# SCH_The-weather-gian_2026-05-14.net
KiCad netlist of a schematic drawn in EasyEDA
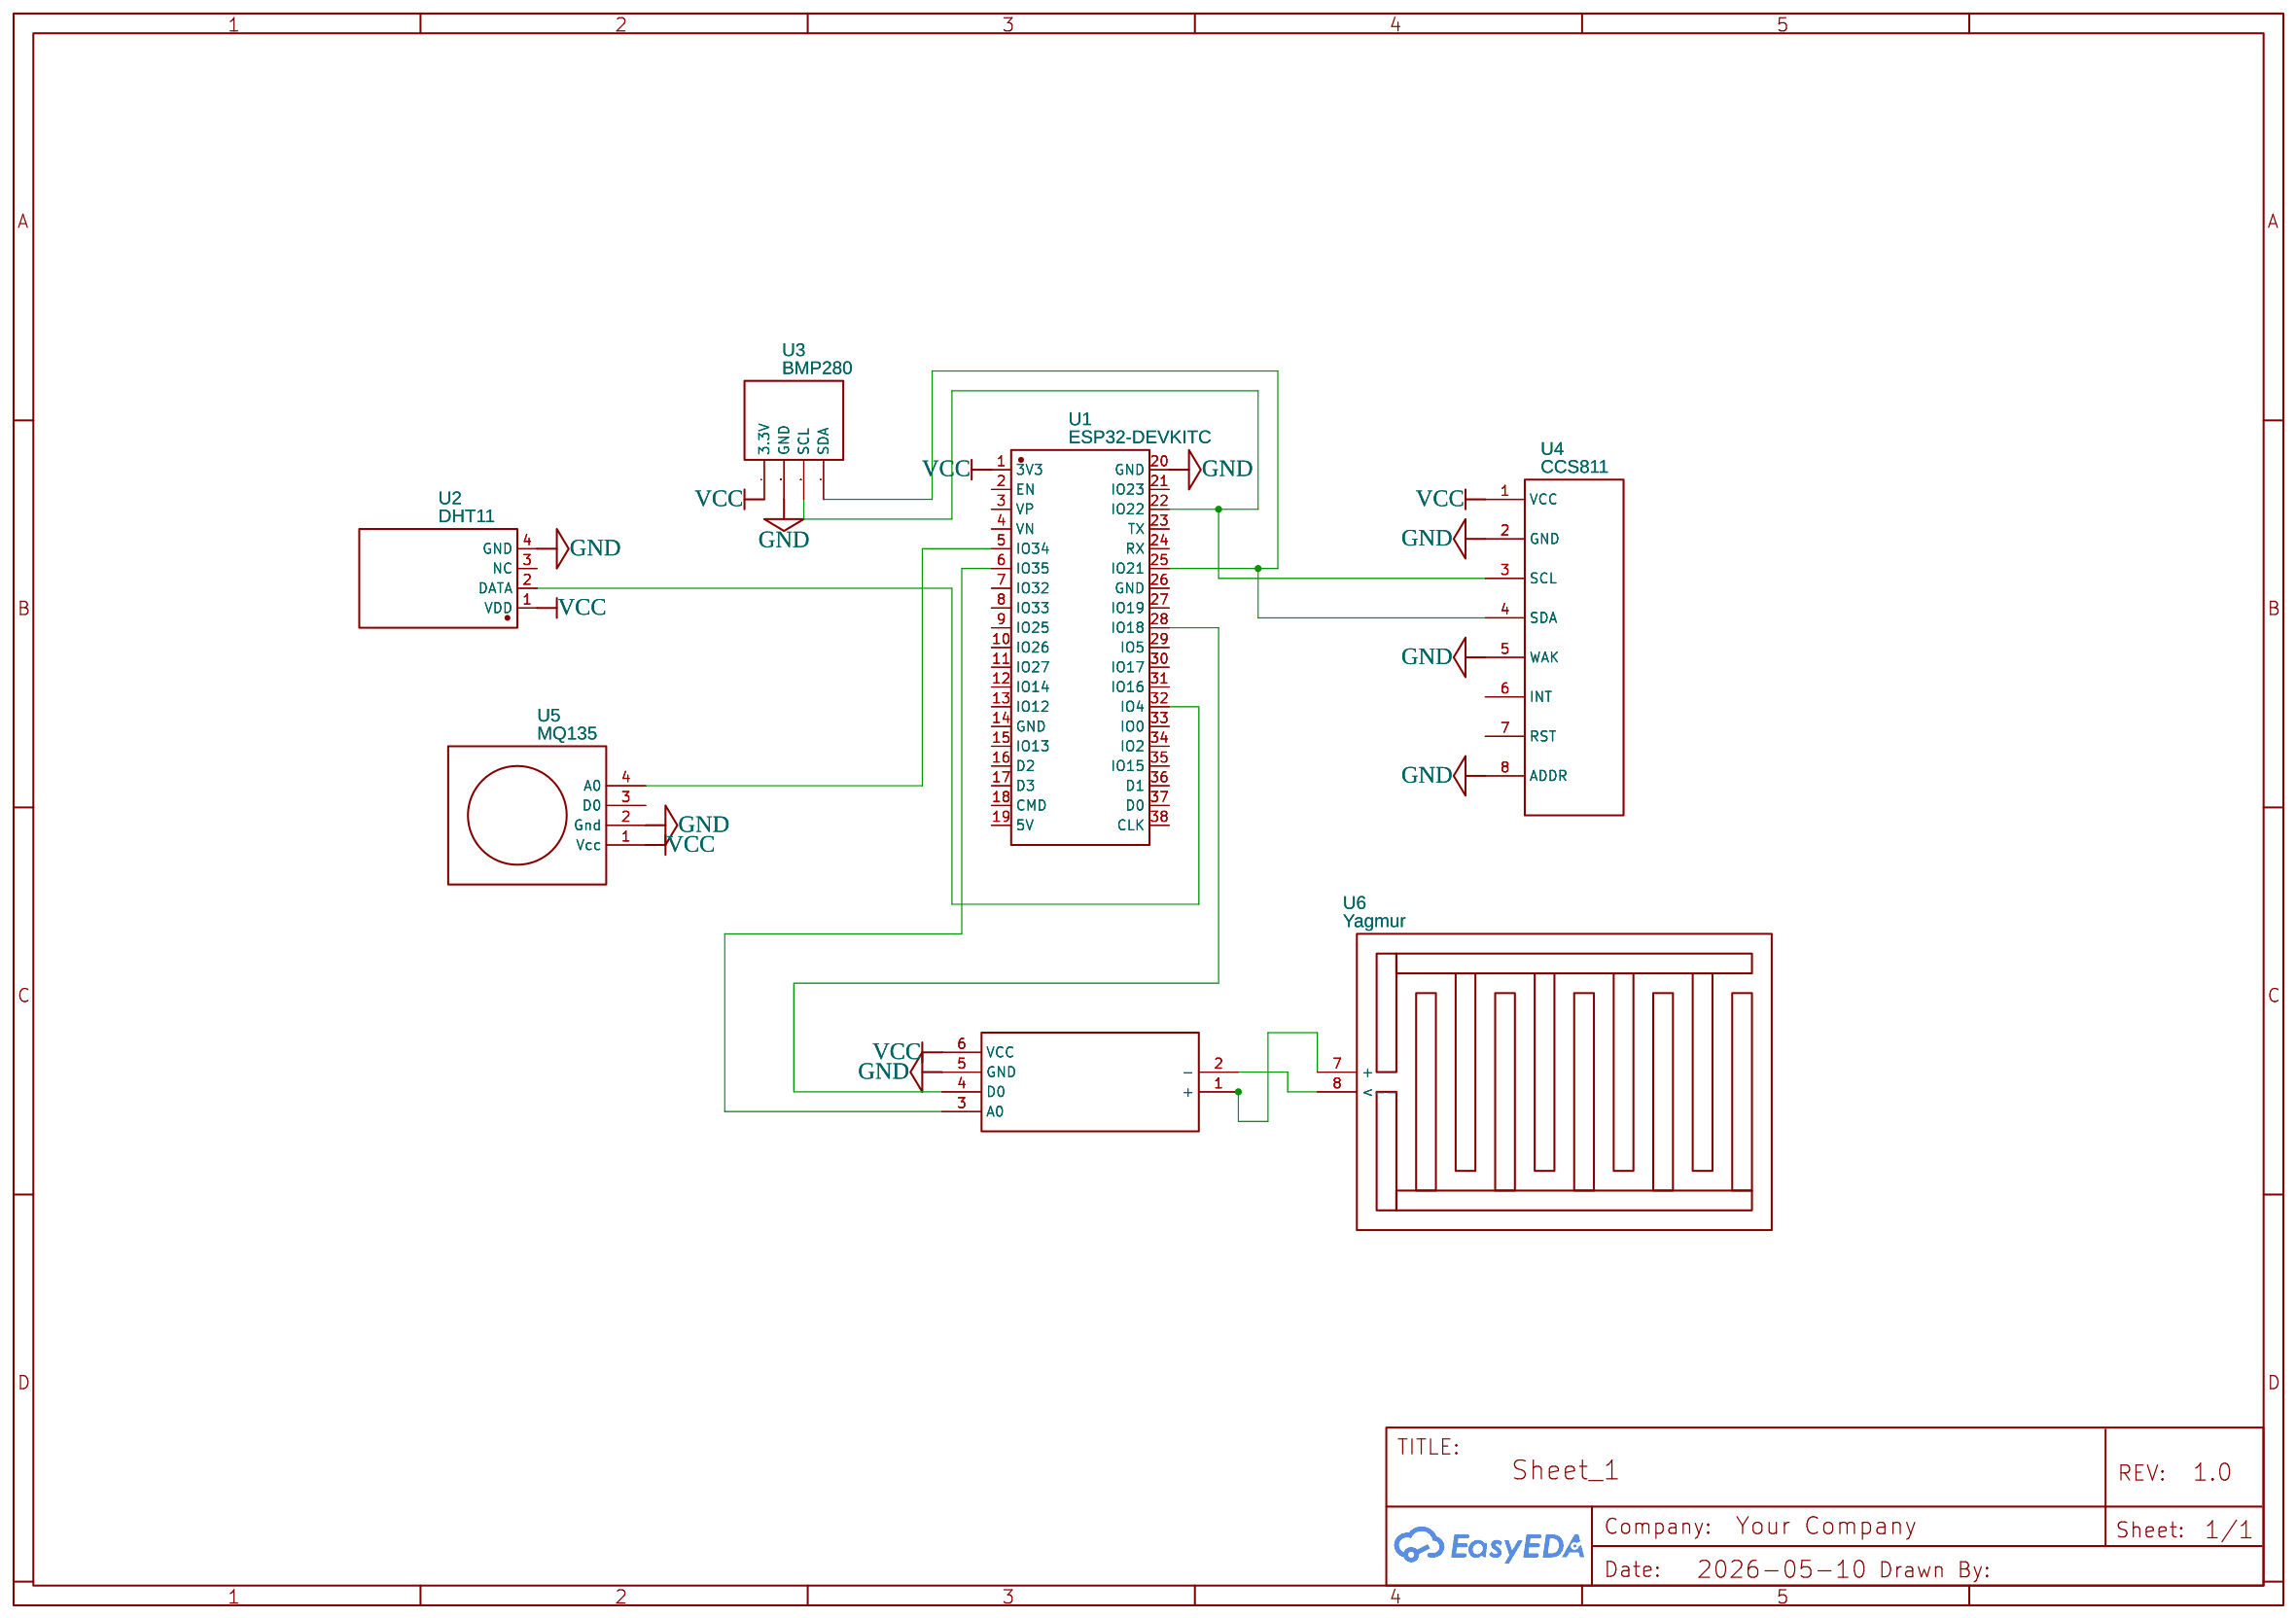
[diagram p0: schematic sheet]

(export (version "E")
  (design (tool "Eeschema 10.0.6"))
  (components
    (comp (ref "U1")
      (value "ESP32-DEVKITC")
      (fields
        (field (name "Manufacturer Part") "ESP32-DevKitC")
        (field (name "Manufacturer") "ESPRESSIF(乐鑫)")
      )
      (libsource (lib "") (part "ESP32-DEVKITC"))
    )
    (comp (ref "U2")
      (value "DHT11")
      (fields (field (name "Manufacturer") "广州奥松"))
      (libsource (lib "") (part "DHT11"))
    )
    (comp (ref "U3") (value "BMP280") (libsource (lib "") (part "BMP280")))
    (comp (ref "U4")
      (value "CCS811")
      (fields (field (name "Manufacturer Part") "CO2_SENS"))
      (libsource (lib "") (part "CCS811"))
    )
    (comp (ref "U5") (value "MQ135") (libsource (lib "") (part "MQ135")))
    (comp (ref "U6") (value "Yagmur") (libsource (lib "") (part "Yagmur")))
  )
  (nets
    (net (code "1") (name "GND") (class "Default")
      (node (ref "U1") (pin "20") (pinfunction "GND_20") (pintype "unspecified"))
      (node (ref "U2") (pin "4") (pinfunction "GND_4") (pintype "unspecified"))
      (node (ref "U3") (pin "6") (pinfunction "GND_6") (pintype "unspecified"))
      (node (ref "U4") (pin "2") (pinfunction "GND_2") (pintype "unspecified"))
      (node (ref "U4") (pin "5") (pinfunction "WAK_5") (pintype "unspecified"))
      (node (ref "U4") (pin "8") (pinfunction "ADDR_8") (pintype "unspecified"))
      (node (ref "U5") (pin "2") (pinfunction "Gnd_2") (pintype "unspecified"))
      (node (ref "U6") (pin "5") (pinfunction "GND_5") (pintype "unspecified"))
    )
    (net (code "2") (name "Net-(U1-IO4)") (class "Default")
      (node (ref "U1") (pin "32") (pinfunction "IO4_32") (pintype "unspecified"))
      (node (ref "U2") (pin "2") (pinfunction "DATA_2") (pintype "unspecified"))
    )
    (net (code "3") (name "Net-(U1-IO18)") (class "Default")
      (node (ref "U1") (pin "28") (pinfunction "IO18_28") (pintype "unspecified"))
      (node (ref "U6") (pin "4") (pinfunction "D0_4") (pintype "unspecified"))
    )
    (net (code "4") (name "Net-(U1-IO21)") (class "Default")
      (node (ref "U1") (pin "25") (pinfunction "IO21_25") (pintype "unspecified"))
      (node (ref "U3") (pin "4") (pinfunction "SDA_4") (pintype "unspecified"))
      (node (ref "U4") (pin "4") (pinfunction "SDA_4") (pintype "unspecified"))
    )
    (net (code "5") (name "Net-(U1-IO22)") (class "Default")
      (node (ref "U1") (pin "22") (pinfunction "IO22_22") (pintype "unspecified"))
      (node (ref "U3") (pin "5") (pinfunction "SCL_5") (pintype "unspecified"))
      (node (ref "U4") (pin "3") (pinfunction "SCL_3") (pintype "unspecified"))
    )
    (net (code "6") (name "Net-(U1-IO34)") (class "Default")
      (node (ref "U1") (pin "5") (pinfunction "IO34_5") (pintype "unspecified"))
      (node (ref "U5") (pin "4") (pinfunction "A0_4") (pintype "unspecified"))
    )
    (net (code "7") (name "Net-(U1-IO35)") (class "Default")
      (node (ref "U1") (pin "6") (pinfunction "IO35_6") (pintype "unspecified"))
      (node (ref "U6") (pin "3") (pinfunction "A0_3") (pintype "unspecified"))
    )
    (net (code "8") (name "Net-(U6-+-Pad1)") (class "Default")
      (node (ref "U6") (pin "1") (pinfunction "+_1") (pintype "unspecified"))
      (node (ref "U6") (pin "7") (pinfunction "+_7") (pintype "unspecified"))
    )
    (net (code "9") (name "Net-(U6--)") (class "Default")
      (node (ref "U6") (pin "2") (pinfunction "-_2") (pintype "unspecified"))
      (node (ref "U6") (pin "8") (pinfunction "<--_8") (pintype "unspecified"))
    )
    (net (code "10") (name "VCC") (class "Default")
      (node (ref "U1") (pin "1") (pinfunction "3V3_1") (pintype "unspecified"))
      (node (ref "U2") (pin "1") (pinfunction "VDD_1") (pintype "unspecified"))
      (node (ref "U3") (pin "7") (pinfunction "3.3V_7") (pintype "unspecified"))
      (node (ref "U4") (pin "1") (pinfunction "VCC_1") (pintype "unspecified"))
      (node (ref "U5") (pin "1") (pinfunction "Vcc_1") (pintype "unspecified"))
      (node (ref "U6") (pin "6") (pinfunction "VCC_6") (pintype "unspecified"))
    )
    (net (code "11") (name "unconnected-(U1-5V-Pad19)") (class "Default")
      (node (ref "U1") (pin "19") (pinfunction "5V_19") (pintype "unspecified"))
    )
    (net (code "12") (name "unconnected-(U1-CLK-Pad38)") (class "Default")
      (node (ref "U1") (pin "38") (pinfunction "CLK_38") (pintype "unspecified"))
    )
    (net (code "13") (name "unconnected-(U1-CMD-Pad18)") (class "Default")
      (node (ref "U1") (pin "18") (pinfunction "CMD_18") (pintype "unspecified"))
    )
    (net (code "14") (name "unconnected-(U1-D0-Pad37)") (class "Default")
      (node (ref "U1") (pin "37") (pinfunction "D0_37") (pintype "unspecified"))
    )
    (net (code "15") (name "unconnected-(U1-D1-Pad36)") (class "Default")
      (node (ref "U1") (pin "36") (pinfunction "D1_36") (pintype "unspecified"))
    )
    (net (code "16") (name "unconnected-(U1-D2-Pad16)") (class "Default")
      (node (ref "U1") (pin "16") (pinfunction "D2_16") (pintype "unspecified"))
    )
    (net (code "17") (name "unconnected-(U1-D3-Pad17)") (class "Default")
      (node (ref "U1") (pin "17") (pinfunction "D3_17") (pintype "unspecified"))
    )
    (net (code "18") (name "unconnected-(U1-EN-Pad2)") (class "Default")
      (node (ref "U1") (pin "2") (pinfunction "EN_2") (pintype "unspecified"))
    )
    (net (code "19") (name "unconnected-(U1-GND-Pad14)") (class "Default")
      (node (ref "U1") (pin "14") (pinfunction "GND_14") (pintype "unspecified"))
    )
    (net (code "20") (name "unconnected-(U1-GND-Pad26)") (class "Default")
      (node (ref "U1") (pin "26") (pinfunction "GND_26") (pintype "unspecified"))
    )
    (net (code "21") (name "unconnected-(U1-IO0-Pad33)") (class "Default")
      (node (ref "U1") (pin "33") (pinfunction "IO0_33") (pintype "unspecified"))
    )
    (net (code "22") (name "unconnected-(U1-IO2-Pad34)") (class "Default")
      (node (ref "U1") (pin "34") (pinfunction "IO2_34") (pintype "unspecified"))
    )
    (net (code "23") (name "unconnected-(U1-IO5-Pad29)") (class "Default")
      (node (ref "U1") (pin "29") (pinfunction "IO5_29") (pintype "unspecified"))
    )
    (net (code "24") (name "unconnected-(U1-IO12-Pad13)") (class "Default")
      (node (ref "U1") (pin "13") (pinfunction "IO12_13") (pintype "unspecified"))
    )
    (net (code "25") (name "unconnected-(U1-IO13-Pad15)") (class "Default")
      (node (ref "U1") (pin "15") (pinfunction "IO13_15") (pintype "unspecified"))
    )
    (net (code "26") (name "unconnected-(U1-IO14-Pad12)") (class "Default")
      (node (ref "U1") (pin "12") (pinfunction "IO14_12") (pintype "unspecified"))
    )
    (net (code "27") (name "unconnected-(U1-IO15-Pad35)") (class "Default")
      (node (ref "U1") (pin "35") (pinfunction "IO15_35") (pintype "unspecified"))
    )
    (net (code "28") (name "unconnected-(U1-IO16-Pad31)") (class "Default")
      (node (ref "U1") (pin "31") (pinfunction "IO16_31") (pintype "unspecified"))
    )
    (net (code "29") (name "unconnected-(U1-IO17-Pad30)") (class "Default")
      (node (ref "U1") (pin "30") (pinfunction "IO17_30") (pintype "unspecified"))
    )
    (net (code "30") (name "unconnected-(U1-IO19-Pad27)") (class "Default")
      (node (ref "U1") (pin "27") (pinfunction "IO19_27") (pintype "unspecified"))
    )
    (net (code "31") (name "unconnected-(U1-IO23-Pad21)") (class "Default")
      (node (ref "U1") (pin "21") (pinfunction "IO23_21") (pintype "unspecified"))
    )
    (net (code "32") (name "unconnected-(U1-IO25-Pad9)") (class "Default")
      (node (ref "U1") (pin "9") (pinfunction "IO25_9") (pintype "unspecified"))
    )
    (net (code "33") (name "unconnected-(U1-IO26-Pad10)") (class "Default")
      (node (ref "U1") (pin "10") (pinfunction "IO26_10") (pintype "unspecified"))
    )
    (net (code "34") (name "unconnected-(U1-IO27-Pad11)") (class "Default")
      (node (ref "U1") (pin "11") (pinfunction "IO27_11") (pintype "unspecified"))
    )
    (net (code "35") (name "unconnected-(U1-IO32-Pad7)") (class "Default")
      (node (ref "U1") (pin "7") (pinfunction "IO32_7") (pintype "unspecified"))
    )
    (net (code "36") (name "unconnected-(U1-IO33-Pad8)") (class "Default")
      (node (ref "U1") (pin "8") (pinfunction "IO33_8") (pintype "unspecified"))
    )
    (net (code "37") (name "unconnected-(U1-RX-Pad24)") (class "Default")
      (node (ref "U1") (pin "24") (pinfunction "RX_24") (pintype "unspecified"))
    )
    (net (code "38") (name "unconnected-(U1-TX-Pad23)") (class "Default")
      (node (ref "U1") (pin "23") (pinfunction "TX_23") (pintype "unspecified"))
    )
    (net (code "39") (name "unconnected-(U1-VN-Pad4)") (class "Default")
      (node (ref "U1") (pin "4") (pinfunction "VN_4") (pintype "unspecified"))
    )
    (net (code "40") (name "unconnected-(U1-VP-Pad3)") (class "Default")
      (node (ref "U1") (pin "3") (pinfunction "VP_3") (pintype "unspecified"))
    )
    (net (code "41") (name "unconnected-(U2-NC-Pad3)") (class "Default")
      (node (ref "U2") (pin "3") (pinfunction "NC_3") (pintype "unspecified"))
    )
    (net (code "42") (name "unconnected-(U4-INT-Pad6)") (class "Default")
      (node (ref "U4") (pin "6") (pinfunction "INT_6") (pintype "unspecified"))
    )
    (net (code "43") (name "unconnected-(U4-RST-Pad7)") (class "Default")
      (node (ref "U4") (pin "7") (pinfunction "RST_7") (pintype "unspecified"))
    )
    (net (code "44") (name "unconnected-(U5-D0-Pad3)") (class "Default")
      (node (ref "U5") (pin "3") (pinfunction "D0_3") (pintype "unspecified"))
    )
  )
)
